# ACCESSORY.net
KiCad netlist of a schematic drawn in Altium Designer
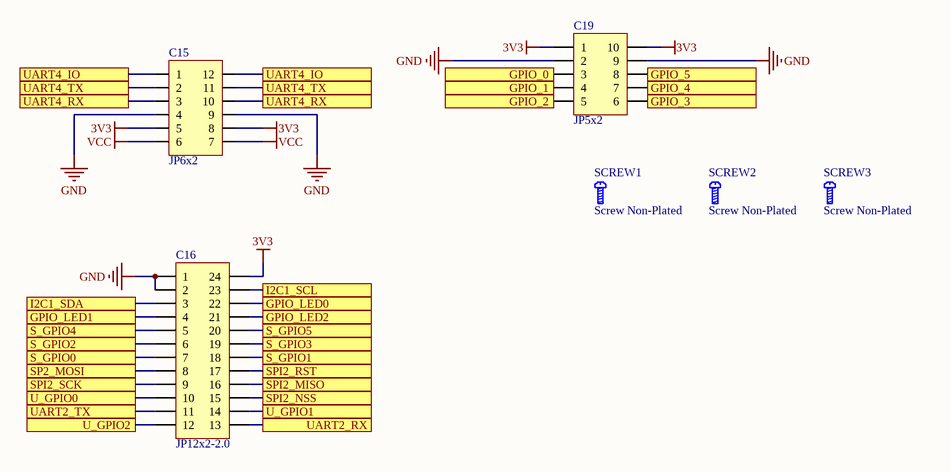
[diagram p0: ACCESSORY.SchDoc]

(export (version "E")
  (design (tool "Eeschema 10.0.6"))
  (components
    (comp (ref "C15")
      (value "JP6x2")
      (footprint "JP6-D2T")
      (description "WR-PHD 2.54 mm Dual Socket Header")
      (fields
        (field (name "MANUFACTURER") "Würth Elektronik eiSos GmbH")
        (field (name "PARTNO") "61301221821")
        (field (name "CREATED BY") "Karrer Zheng")
      )
      (libsource (lib "LIBRARY") (part "JP6x2"))
    )
    (comp (ref "C16")
      (value "JP12x2-2.0")
      (footprint "J12-D2T")
      (description "WR-PHD 2.00 mm Dual Pin Header")
      (fields
        (field (name "MANUFACTURER") "Würth Elektronik eiSos GmbH")
        (field (name "PARTNO") "62002421121")
        (field (name "CREATED BY") "Karrer Zheng")
      )
      (libsource (lib "LIBRARY") (part "JP12x2-2.0"))
    )
    (comp (ref "C19")
      (value "JP5x2")
      (footprint "JP5-D2T")
      (description "WR-PHD 2.54 mm Dual Socket Header")
      (fields
        (field (name "MANUFACTURER") "Würth Elektronik eiSos GmbH")
        (field (name "PARTNO") "61301021821")
        (field (name "CREATED BY") "Karrer Zheng")
      )
      (libsource (lib "LIBRARY") (part "JP5x2"))
    )
    (comp (ref "SCREW1")
      (value "Screw Non-Plated")
      (footprint "ThanhNT:SCREW_NON-PLATED_2MM")
      (libsource (lib "ThanhNT") (part "SCREW_NON-PLATED"))
    )
    (comp (ref "SCREW2")
      (value "Screw Non-Plated")
      (footprint "ThanhNT:SCREW_NON-PLATED_2MM")
      (libsource (lib "ThanhNT") (part "SCREW_NON-PLATED"))
    )
    (comp (ref "SCREW3")
      (value "Screw Non-Plated")
      (footprint "ThanhNT:SCREW_NON-PLATED_2MM")
      (libsource (lib "ThanhNT") (part "SCREW_NON-PLATED"))
    )
  )
  (nets
    (net (code "1") (name "/GPIO_0") (class "Default")
      (node (ref "C19") (pin "3") (pinfunction "3_3") (pintype "passive"))
    )
    (net (code "2") (name "/GPIO_1") (class "Default")
      (node (ref "C19") (pin "4") (pinfunction "4_4") (pintype "passive"))
    )
    (net (code "3") (name "/GPIO_2") (class "Default")
      (node (ref "C19") (pin "5") (pinfunction "5_5") (pintype "passive"))
    )
    (net (code "4") (name "/GPIO_3") (class "Default")
      (node (ref "C19") (pin "6") (pinfunction "6_6") (pintype "passive"))
    )
    (net (code "5") (name "/GPIO_4") (class "Default")
      (node (ref "C19") (pin "7") (pinfunction "7_7") (pintype "passive"))
    )
    (net (code "6") (name "/GPIO_5") (class "Default")
      (node (ref "C19") (pin "8") (pinfunction "8_8") (pintype "passive"))
    )
    (net (code "7") (name "/GPIO_LED0") (class "Default")
      (node (ref "C16") (pin "22") (pinfunction "22_22") (pintype "passive"))
    )
    (net (code "8") (name "/GPIO_LED1") (class "Default")
      (node (ref "C16") (pin "4") (pinfunction "4_4") (pintype "passive"))
    )
    (net (code "9") (name "/GPIO_LED2") (class "Default")
      (node (ref "C16") (pin "21") (pinfunction "21_21") (pintype "passive"))
    )
    (net (code "10") (name "/I2C1_SCL") (class "Default")
      (node (ref "C16") (pin "23") (pinfunction "23_23") (pintype "passive"))
    )
    (net (code "11") (name "/I2C1_SDA") (class "Default")
      (node (ref "C16") (pin "3") (pinfunction "3_3") (pintype "passive"))
    )
    (net (code "12") (name "/SP2_MOSI") (class "Default")
      (node (ref "C16") (pin "8") (pinfunction "8_8") (pintype "passive"))
    )
    (net (code "13") (name "/SPI2_MISO") (class "Default")
      (node (ref "C16") (pin "16") (pinfunction "16_16") (pintype "passive"))
    )
    (net (code "14") (name "/SPI2_NSS") (class "Default")
      (node (ref "C16") (pin "15") (pinfunction "15_15") (pintype "passive"))
    )
    (net (code "15") (name "/SPI2_RST") (class "Default")
      (node (ref "C16") (pin "17") (pinfunction "17_17") (pintype "passive"))
    )
    (net (code "16") (name "/SPI2_SCK") (class "Default")
      (node (ref "C16") (pin "9") (pinfunction "9_9") (pintype "passive"))
    )
    (net (code "17") (name "/S_GPIO0") (class "Default")
      (node (ref "C16") (pin "7") (pinfunction "7_7") (pintype "passive"))
    )
    (net (code "18") (name "/S_GPIO1") (class "Default")
      (node (ref "C16") (pin "18") (pinfunction "18_18") (pintype "passive"))
    )
    (net (code "19") (name "/S_GPIO2") (class "Default")
      (node (ref "C16") (pin "6") (pinfunction "6_6") (pintype "passive"))
    )
    (net (code "20") (name "/S_GPIO3") (class "Default")
      (node (ref "C16") (pin "19") (pinfunction "19_19") (pintype "passive"))
    )
    (net (code "21") (name "/S_GPIO4") (class "Default")
      (node (ref "C16") (pin "5") (pinfunction "5_5") (pintype "passive"))
    )
    (net (code "22") (name "/S_GPIO5") (class "Default")
      (node (ref "C16") (pin "20") (pinfunction "20_20") (pintype "passive"))
    )
    (net (code "23") (name "/UART2_RX") (class "Default")
      (node (ref "C16") (pin "13") (pinfunction "13_13") (pintype "passive"))
    )
    (net (code "24") (name "/UART2_TX") (class "Default")
      (node (ref "C16") (pin "11") (pinfunction "11_11") (pintype "passive"))
    )
    (net (code "25") (name "/UART4_IO") (class "Default")
      (node (ref "C15") (pin "1") (pinfunction "1_1") (pintype "passive"))
      (node (ref "C15") (pin "12") (pinfunction "12_12") (pintype "passive"))
    )
    (net (code "26") (name "/UART4_RX") (class "Default")
      (node (ref "C15") (pin "10") (pinfunction "10_10") (pintype "passive"))
      (node (ref "C15") (pin "3") (pinfunction "3_3") (pintype "passive"))
    )
    (net (code "27") (name "/UART4_TX") (class "Default")
      (node (ref "C15") (pin "11") (pinfunction "11_11") (pintype "passive"))
      (node (ref "C15") (pin "2") (pinfunction "2_2") (pintype "passive"))
    )
    (net (code "28") (name "/U_GPIO0") (class "Default")
      (node (ref "C16") (pin "10") (pinfunction "10_10") (pintype "passive"))
    )
    (net (code "29") (name "/U_GPIO1") (class "Default")
      (node (ref "C16") (pin "14") (pinfunction "14_14") (pintype "passive"))
    )
    (net (code "30") (name "/U_GPIO2") (class "Default")
      (node (ref "C16") (pin "12") (pinfunction "12_12") (pintype "passive"))
    )
    (net (code "31") (name "3V3") (class "Default")
      (node (ref "C15") (pin "5") (pinfunction "5_5") (pintype "passive"))
      (node (ref "C15") (pin "8") (pinfunction "8_8") (pintype "passive"))
      (node (ref "C16") (pin "24") (pinfunction "24_24") (pintype "passive"))
      (node (ref "C19") (pin "1") (pinfunction "1_1") (pintype "passive"))
      (node (ref "C19") (pin "10") (pinfunction "10_10") (pintype "passive"))
    )
    (net (code "32") (name "GND") (class "Default")
      (node (ref "C15") (pin "4") (pinfunction "4_4") (pintype "passive"))
      (node (ref "C15") (pin "9") (pinfunction "9_9") (pintype "passive"))
      (node (ref "C16") (pin "1") (pinfunction "1_1") (pintype "passive"))
      (node (ref "C16") (pin "2") (pinfunction "2_2") (pintype "passive"))
      (node (ref "C19") (pin "2") (pinfunction "2_2") (pintype "passive"))
      (node (ref "C19") (pin "9") (pinfunction "9_9") (pintype "passive"))
    )
    (net (code "33") (name "VCC") (class "Default")
      (node (ref "C15") (pin "6") (pinfunction "6_6") (pintype "passive"))
      (node (ref "C15") (pin "7") (pinfunction "7_7") (pintype "passive"))
    )
  )
)
